# sepic.net
KiCad netlist of a schematic drawn in EAGLE
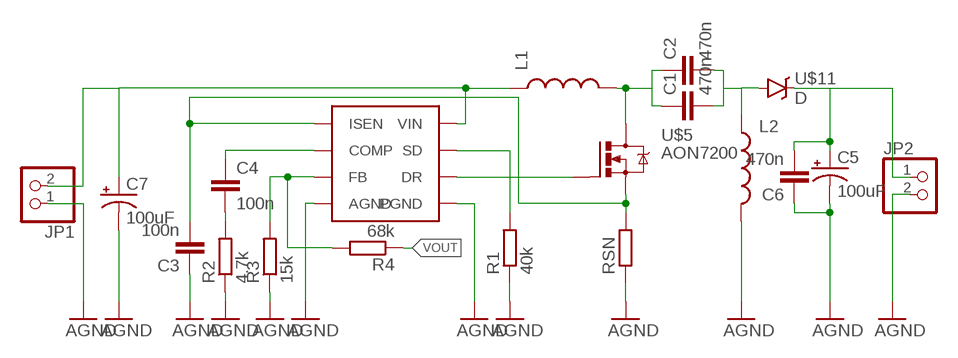
[diagram p0: schematic, sheet 1]

(export (version "E")
  (design (tool "Eeschema 10.0.6"))
  (components
    (comp (ref "C1")
      (value "470n")
      (footprint "eagle-import:C0805")
      (libsource (lib "eagle-import") (part "CC0805"))
    )
    (comp (ref "C2")
      (value "470n")
      (footprint "eagle-import:C0805")
      (libsource (lib "eagle-import") (part "CC0805"))
    )
    (comp (ref "C3")
      (value "100n")
      (footprint "eagle-import:C0805")
      (libsource (lib "eagle-import") (part "CC0805"))
    )
    (comp (ref "C4")
      (value "100n")
      (footprint "eagle-import:C0805")
      (libsource (lib "eagle-import") (part "CC0805"))
    )
    (comp (ref "C5")
      (value "100uF")
      (footprint "eagle-import:NIC_10X10.5_CAP")
      (libsource (lib "eagle-import") (part "100UF-63V-20%(ELECT)"))
    )
    (comp (ref "C6")
      (value "470n")
      (footprint "eagle-import:C0805")
      (libsource (lib "eagle-import") (part "CC0805"))
    )
    (comp (ref "C7")
      (value "100uF")
      (footprint "eagle-import:NIC_10X10.5_CAP")
      (libsource (lib "eagle-import") (part "100UF-63V-20%(ELECT)"))
    )
    (comp (ref "JP1")
      (value "PINHD-1X02_2.54")
      (footprint "eagle-import:1X02")
      (libsource (lib "eagle-import") (part "PINHD-1X02_2.54"))
    )
    (comp (ref "JP2")
      (value "PINHD-1X02_2.54")
      (footprint "eagle-import:1X02")
      (libsource (lib "eagle-import") (part "PINHD-1X02_2.54"))
    )
    (comp (ref "L1")
      (value "INDUCTORSRU1038")
      (footprint "eagle-import:SRU1038")
      (libsource (lib "eagle-import") (part "INDUCTORSRU1038"))
    )
    (comp (ref "L2")
      (value "INDUCTORSRU1038")
      (footprint "eagle-import:SRU1038")
      (libsource (lib "eagle-import") (part "INDUCTORSRU1038"))
    )
    (comp (ref "R1")
      (value "40k")
      (footprint "eagle-import:0603")
      (libsource (lib "eagle-import") (part "R0603"))
    )
    (comp (ref "R2")
      (value "4.7k")
      (footprint "eagle-import:R0805")
      (libsource (lib "eagle-import") (part "R0805"))
    )
    (comp (ref "R3")
      (value "15k")
      (footprint "eagle-import:R0805")
      (libsource (lib "eagle-import") (part "R0805"))
    )
    (comp (ref "R4")
      (value "68k")
      (footprint "eagle-import:R0805")
      (libsource (lib "eagle-import") (part "R0805"))
    )
    (comp (ref "RSN")
      (value "R2512")
      (footprint "eagle-import:R2512")
      (libsource (lib "eagle-import") (part "R2512"))
    )
    (comp (ref "U$1")
      (value "LM3488")
      (footprint "eagle-import:S-PDSO-G8")
      (libsource (lib "eagle-import") (part "LM3488"))
    )
    (comp (ref "U$5")
      (value "AON7200")
      (footprint "eagle-import:DFN3X3")
      (libsource (lib "eagle-import") (part "AON7200"))
    )
    (comp (ref "U$11")
      (value "D")
      (footprint "eagle-import:SMA-DIODE")
      (libsource (lib "eagle-import") (part "SS14"))
    )
  )
  (nets
    (net (code "1") (name "AGND") (class "Default")
      (node (ref "C3") (pin "1") (pinfunction "1_1") (pintype "passive"))
      (node (ref "C5") (pin "-") (pinfunction "-_-") (pintype "passive"))
      (node (ref "C6") (pin "1") (pinfunction "1_1") (pintype "passive"))
      (node (ref "C7") (pin "-") (pinfunction "-_-") (pintype "passive"))
      (node (ref "JP1") (pin "1") (pinfunction "1_1") (pintype "passive"))
      (node (ref "JP2") (pin "2") (pinfunction "2_2") (pintype "passive"))
      (node (ref "L2") (pin "2") (pinfunction "2_2") (pintype "passive"))
      (node (ref "R1") (pin "1") (pinfunction "1_1") (pintype "passive"))
      (node (ref "R2") (pin "1") (pinfunction "1_1") (pintype "passive"))
      (node (ref "R3") (pin "1") (pinfunction "1_1") (pintype "passive"))
      (node (ref "RSN") (pin "P$1") (pinfunction "1_P$1") (pintype "passive"))
      (node (ref "U$1") (pin "4") (pinfunction "AGND_4") (pintype "bidirectional"))
      (node (ref "U$1") (pin "5") (pinfunction "PGND_5") (pintype "bidirectional"))
    )
    (net (code "2") (name "Net-(C1-Pad1)") (class "Default")
      (node (ref "C1") (pin "1") (pinfunction "1_1") (pintype "passive"))
      (node (ref "C2") (pin "1") (pinfunction "1_1") (pintype "passive"))
      (node (ref "L1") (pin "2") (pinfunction "2_2") (pintype "passive"))
      (node (ref "U$5") (pin "D") (pinfunction "D_D") (pintype "passive"))
      (node (ref "U$5") (pin "D:1") (pinfunction "D_D:1") (pintype "passive"))
      (node (ref "U$5") (pin "D:2") (pinfunction "D_D:2") (pintype "passive"))
      (node (ref "U$5") (pin "D:3") (pinfunction "D_D:3") (pintype "passive"))
      (node (ref "U$5") (pin "D:4") (pinfunction "D_D:4") (pintype "passive"))
      (node (ref "U$5") (pin "D:5") (pinfunction "D_D:5") (pintype "passive"))
      (node (ref "U$5") (pin "D:6") (pinfunction "D_D:6") (pintype "passive"))
    )
    (net (code "3") (name "Net-(C1-Pad2)") (class "Default")
      (node (ref "C1") (pin "2") (pinfunction "2_2") (pintype "passive"))
      (node (ref "C2") (pin "2") (pinfunction "2_2") (pintype "passive"))
      (node (ref "L2") (pin "1") (pinfunction "1_1") (pintype "passive"))
      (node (ref "U$11") (pin "A") (pinfunction "A_A") (pintype "passive"))
    )
    (net (code "4") (name "Net-(C4-Pad2)") (class "Default")
      (node (ref "C4") (pin "2") (pinfunction "2_2") (pintype "passive"))
      (node (ref "R2") (pin "2") (pinfunction "2_2") (pintype "passive"))
    )
    (net (code "5") (name "Net-(RSN-2)") (class "Default")
      (node (ref "C3") (pin "2") (pinfunction "2_2") (pintype "passive"))
      (node (ref "RSN") (pin "P$2") (pinfunction "2_P$2") (pintype "passive"))
      (node (ref "U$1") (pin "1") (pinfunction "ISEN_1") (pintype "bidirectional"))
      (node (ref "U$5") (pin "S:1") (pinfunction "S_S:1") (pintype "passive"))
      (node (ref "U$5") (pin "S:2") (pinfunction "S_S:2") (pintype "passive"))
      (node (ref "U$5") (pin "S:3") (pinfunction "S_S:3") (pintype "passive"))
    )
    (net (code "6") (name "Net-(U$1-COMP)") (class "Default")
      (node (ref "C4") (pin "1") (pinfunction "1_1") (pintype "passive"))
      (node (ref "U$1") (pin "2") (pinfunction "COMP_2") (pintype "bidirectional"))
    )
    (net (code "7") (name "Net-(U$1-DR)") (class "Default")
      (node (ref "U$1") (pin "6") (pinfunction "DR_6") (pintype "bidirectional"))
      (node (ref "U$5") (pin "G") (pinfunction "G_G") (pintype "passive"))
    )
    (net (code "8") (name "Net-(U$1-FB)") (class "Default")
      (node (ref "R3") (pin "2") (pinfunction "2_2") (pintype "passive"))
      (node (ref "R4") (pin "2") (pinfunction "2_2") (pintype "passive"))
      (node (ref "U$1") (pin "3") (pinfunction "FB_3") (pintype "bidirectional"))
    )
    (net (code "9") (name "Net-(U$1-SD)") (class "Default")
      (node (ref "R1") (pin "2") (pinfunction "2_2") (pintype "passive"))
      (node (ref "U$1") (pin "7") (pinfunction "SD_7") (pintype "bidirectional"))
    )
    (net (code "10") (name "Net-(U$1-VIN)") (class "Default")
      (node (ref "C7") (pin "+") (pinfunction "+_+") (pintype "passive"))
      (node (ref "JP1") (pin "2") (pinfunction "2_2") (pintype "passive"))
      (node (ref "L1") (pin "1") (pinfunction "1_1") (pintype "passive"))
      (node (ref "U$1") (pin "8") (pinfunction "VIN_8") (pintype "bidirectional"))
    )
    (net (code "11") (name "VOUT") (class "Default")
      (node (ref "C5") (pin "+") (pinfunction "+_+") (pintype "passive"))
      (node (ref "C6") (pin "2") (pinfunction "2_2") (pintype "passive"))
      (node (ref "JP2") (pin "1") (pinfunction "1_1") (pintype "passive"))
      (node (ref "R4") (pin "1") (pinfunction "1_1") (pintype "passive"))
      (node (ref "U$11") (pin "C") (pinfunction "C_C") (pintype "passive"))
    )
  )
)
